# EDR_RFID_READER.net
KiCad netlist of a schematic drawn in Altium Designer
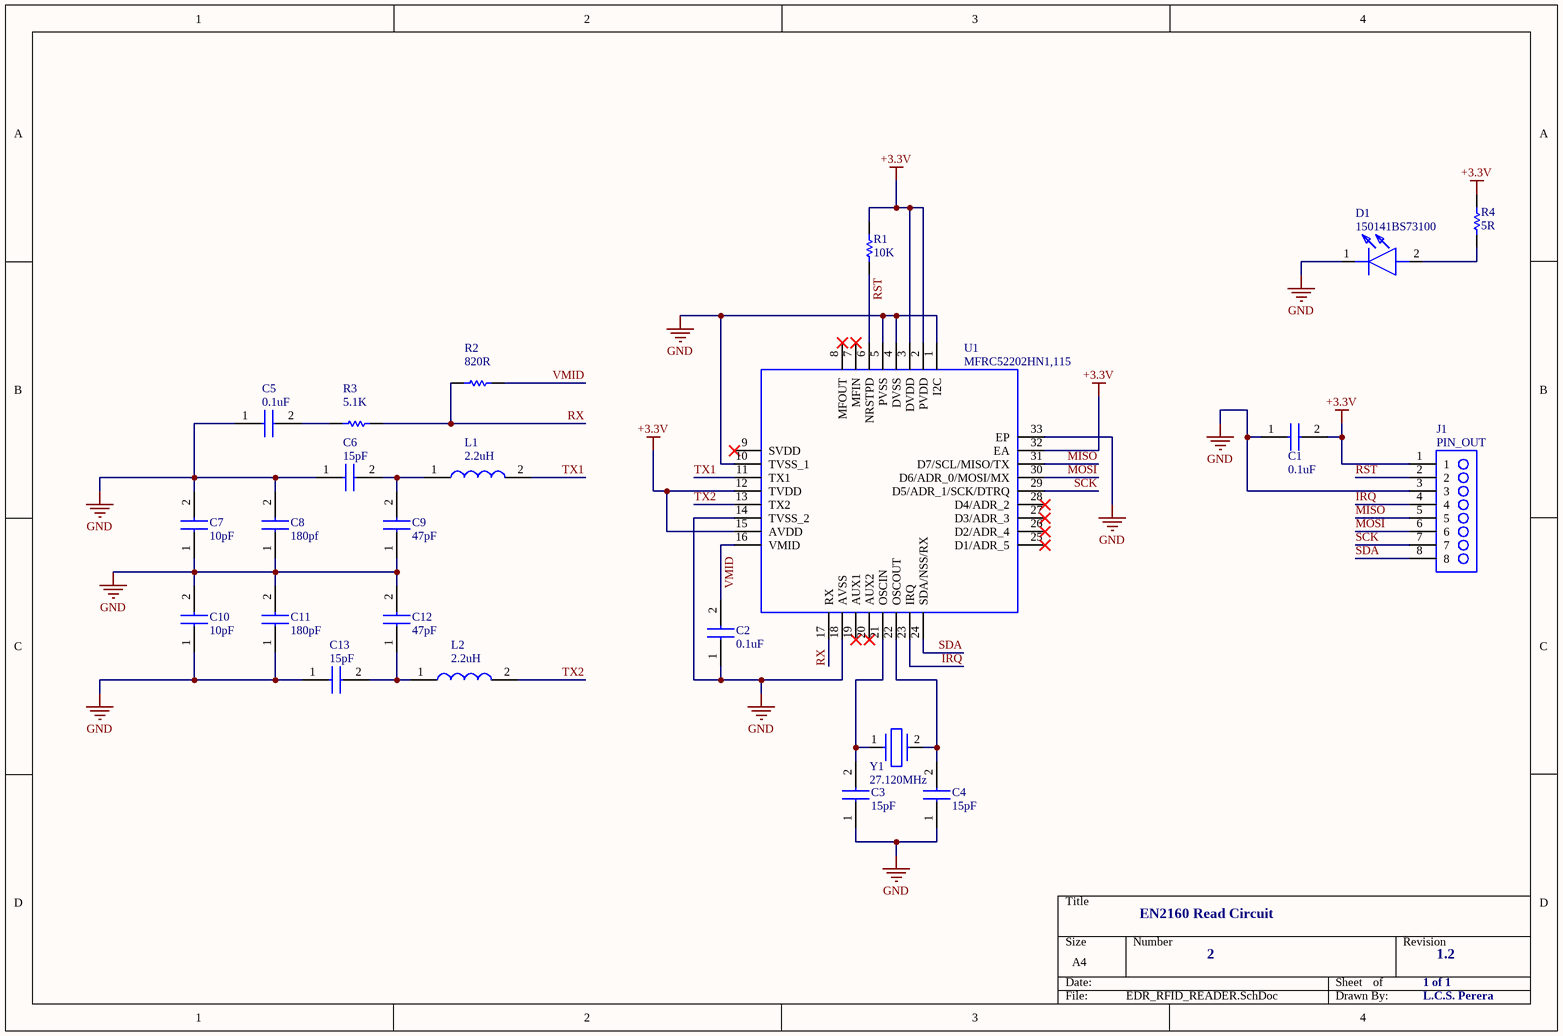
[diagram p0: EDR_RFID_READER.SchDoc]

(export (version "E")
  (design (tool "Eeschema 10.0.6"))
  (components
    (comp (ref "C1")
      (value "0.1uF")
      (footprint "0.1u")
      (description "Capacitor")
      (fields
        (field (name "MANUFACTURER_PART_NUMBER") "C0603C104K1RACTU")
        (field (name "MOUSER PART NUMBER") "80-C0603C104K1RACTU")
      )
      (libsource (lib "Schlib1") (part "0.1uF"))
    )
    (comp (ref "C2")
      (value "0.1uF")
      (footprint "0.1u")
      (description "Capacitor")
      (fields
        (field (name "MANUFACTURER_PART_NUMBER") "C0603C104K1RACTU")
        (field (name "MOUSER PART NUMBER") "80-C0603C104K1RACTU")
      )
      (libsource (lib "Schlib1") (part "0.1uF"))
    )
    (comp (ref "C3")
      (value "15pF")
      (footprint "15pf")
      (description "Capacitor")
      (fields
        (field (name "MANUFACTURER_PART_NUMBER") "C0805X150F4HACAUTO")
        (field (name "MOUSER PART NUMBER") "80-C0805X150F4HAUTO")
      )
      (libsource (lib "Schlib1") (part "C0805X150F4HACAUTO"))
    )
    (comp (ref "C4")
      (value "15pF")
      (footprint "15pf")
      (description "Capacitor")
      (fields
        (field (name "MANUFACTURER_PART_NUMBER") "C0805X150F4HACAUTO")
        (field (name "MOUSER PART NUMBER") "80-C0805X150F4HAUTO")
      )
      (libsource (lib "Schlib1") (part "C0805X150F4HACAUTO"))
    )
    (comp (ref "C5")
      (value "0.1uF")
      (footprint "0.1u")
      (description "Capacitor")
      (fields
        (field (name "MANUFACTURER_PART_NUMBER") "C0603C104K1RACTU")
        (field (name "MOUSER PART NUMBER") "80-C0603C104K1RACTU")
      )
      (libsource (lib "Schlib1") (part "0.1uF"))
    )
    (comp (ref "C6")
      (value "15pF")
      (footprint "15pf")
      (description "Capacitor")
      (fields
        (field (name "MANUFACTURER_PART_NUMBER") "C0805X150F4HACAUTO")
        (field (name "MOUSER PART NUMBER") "80-C0805X150F4HAUTO")
      )
      (libsource (lib "Schlib1") (part "C0805X150F4HACAUTO"))
    )
    (comp (ref "C7")
      (value "10pF")
      (footprint "10pf")
      (fields (field (name "MP") "C0805C100J5GACTU"))
      (libsource (lib "Schlib1") (part "C0805C100J5GACTU"))
    )
    (comp (ref "C8")
      (value "180pf")
      (footprint "15pf")
      (description "Capacitor")
      (fields (field (name "MANUFACTURER_PART_NUMBER") "C0805C181F1GACTU"))
      (libsource (lib "Schlib1") (part "C0805C181F1GACTU"))
    )
    (comp (ref "C9")
      (value "47pF")
      (footprint "47pf")
      (description "Capacitor")
      (fields
        (field (name "MANUFACTURER_PART_NUMBER") "C0805C470JDGACTU")
        (field (name "MOUSER PART NUMBER") "80-C0805C470JDG")
      )
      (libsource (lib "Schlib1") (part "C0805C470JDGACTU"))
    )
    (comp (ref "C10")
      (value "10pF")
      (footprint "10pf")
      (fields (field (name "MP") "C0805C100J5GACTU"))
      (libsource (lib "Schlib1") (part "C0805C100J5GACTU"))
    )
    (comp (ref "C11")
      (value "180pF")
      (footprint "15pf")
      (description "Capacitor")
      (fields (field (name "MANUFACTURER_PART_NUMBER") "C0805C181F1GACTU"))
      (libsource (lib "Schlib1") (part "C0805C181F1GACTU"))
    )
    (comp (ref "C12")
      (value "47pF")
      (footprint "47pf")
      (description "Capacitor")
      (fields
        (field (name "MANUFACTURER_PART_NUMBER") "C0805C470JDGACTU")
        (field (name "MOUSER PART NUMBER") "80-C0805C470JDG")
      )
      (libsource (lib "Schlib1") (part "C0805C470JDGACTU"))
    )
    (comp (ref "C13")
      (value "15pF")
      (footprint "15pf")
      (description "Capacitor")
      (fields
        (field (name "MANUFACTURER_PART_NUMBER") "C0805X150F4HACAUTO")
        (field (name "MOUSER PART NUMBER") "80-C0805X150F4HAUTO")
      )
      (libsource (lib "Schlib1") (part "C0805X150F4HACAUTO"))
    )
    (comp (ref "D1")
      (value "150141BS73100")
      (footprint "LEDM3528X210N")
      (description "LED")
      (fields (field (name "MOUSER PART NUMBER") "710-150141BS73100"))
      (libsource (lib "Schlib1") (part "150141BS73100"))
    )
    (comp (ref "J1")
      (value "PIN_OUT")
      (footprint "8X1")
      (description "Connector")
      (fields
        (field (name "MANUFACTURER_PART_NUMBER") "61300811121")
        (field (name "MOUSER PART NUMBER") "710-61300811121")
      )
      (libsource (lib "Schlib1") (part "61300811121_1"))
    )
    (comp (ref "L1")
      (value "2.2uH")
      (footprint "2.2U")
      (description "Inductor")
      (fields
        (field (name "MANUFACTURER_PART_NUMBER") "ASMPM-0806-2R2M-T")
        (field (name "MOUSER PART NUMBER") "815-ASMPM-0806-2.2MT")
      )
      (libsource (lib "Schlib1") (part "ASMPM-0806-2R2M-T"))
    )
    (comp (ref "L2")
      (value "2.2uH")
      (footprint "2.2U")
      (description "Inductor")
      (fields
        (field (name "MANUFACTURER_PART_NUMBER") "ASMPM-0806-2R2M-T")
        (field (name "MOUSER PART NUMBER") "815-ASMPM-0806-2.2MT")
      )
      (libsource (lib "Schlib1") (part "ASMPM-0806-2R2M-T"))
    )
    (comp (ref "R1")
      (value "10K")
      (footprint "10k")
      (description "Resistor")
      (fields
        (field (name "MANUFACTURER_PART_NUMBER") "CR0805-FX-1002ELF")
        (field (name "MOUSER PART NUMBER") "652-CR0805FX-1002ELF")
      )
      (libsource (lib "Schlib1") (part "CR0805-FX-1002ELF"))
    )
    (comp (ref "R2")
      (value "820R")
      (footprint "820")
      (description "Resistor")
      (fields (field (name "MANUFACTURER_PART_NUMBER") "0805W8F8200T5E"))
      (libsource (lib "Schlib1") (part "0805W8F8200T5E"))
    )
    (comp (ref "R3")
      (value "5.1K")
      (footprint "5.1k")
      (description "Resistor")
      (fields
        (field (name "MANUFACTURER_PART_NUMBER") "CR0805-FX-5101ELF")
        (field (name "MOUSER PART NUMBER") "652-CR0805FX-5101ELF")
      )
      (libsource (lib "Schlib1") (part "CR0805-FX-5101ELF"))
    )
    (comp (ref "R4")
      (value "5R")
      (footprint "1k")
      (description "Resistor")
      (fields
        (field (name "MANUFACTURER_PART_NUMBER") "CHP0805AFX-1002ELF")
        (field (name "MOUSER PART NUMBER") "652-CHP0805AFX1002EL")
      )
      (libsource (lib "Schlib1") (part "CHP0805AFX-1002ELF1k"))
    )
    (comp (ref "U1")
      (value "MFRC52202HN1,115")
      (footprint "MFRC522")
      (description "Integrated Circuit")
      (fields (field (name "MOUSER PART NUMBER") "771-MFRC52202HN1115"))
      (libsource (lib "Schlib1") (part "MFRC52202HN1,115"))
    )
    (comp (ref "Y1")
      (value "27.120MHz")
      (footprint "27.120")
      (description "Crystal or Oscillator")
      (fields
        (field (name "MANUFACTURER_PART_NUMBER") "ABLS-27.120MHZ-B4-F-T")
        (field (name "MOUSER PART NUMBER") "815-ABLS27120MHZB4FT")
      )
      (libsource (lib "Schlib1") (part "ABLS-27.120MHZ-B4-F-T"))
    )
  )
  (nets
    (net (code "1") (name "+3.3V") (class "Default")
      (node (ref "C1") (pin "2") (pinfunction "2_2") (pintype "passive"))
      (node (ref "J1") (pin "1") (pinfunction "1_1") (pintype "passive"))
      (node (ref "R1") (pin "2") (pinfunction "2_2") (pintype "passive"))
      (node (ref "R4") (pin "2") (pinfunction "2_2") (pintype "passive"))
      (node (ref "U1") (pin "12") (pinfunction "TVDD_12") (pintype "passive"))
      (node (ref "U1") (pin "15") (pinfunction "AVDD_15") (pintype "passive"))
      (node (ref "U1") (pin "2") (pinfunction "PVDD_2") (pintype "passive"))
      (node (ref "U1") (pin "3") (pinfunction "DVDD_3") (pintype "passive"))
      (node (ref "U1") (pin "32") (pinfunction "EA_32") (pintype "passive"))
    )
    (net (code "2") (name "/IRQ") (class "Default")
      (node (ref "J1") (pin "4") (pinfunction "4_4") (pintype "passive"))
      (node (ref "U1") (pin "23") (pinfunction "IRQ_23") (pintype "passive"))
    )
    (net (code "3") (name "/MISO") (class "Default")
      (node (ref "J1") (pin "5") (pinfunction "5_5") (pintype "passive"))
      (node (ref "U1") (pin "31") (pinfunction "D7/SCL/MISO/TX_31") (pintype "passive"))
    )
    (net (code "4") (name "/MOSI") (class "Default")
      (node (ref "J1") (pin "6") (pinfunction "6_6") (pintype "passive"))
      (node (ref "U1") (pin "30") (pinfunction "D6/ADR_0/MOSI/MX_30") (pintype "passive"))
    )
    (net (code "5") (name "/RST") (class "Default")
      (node (ref "J1") (pin "2") (pinfunction "2_2") (pintype "passive"))
      (node (ref "R1") (pin "1") (pinfunction "1_1") (pintype "passive"))
      (node (ref "U1") (pin "6") (pinfunction "NRSTPD_6") (pintype "passive"))
    )
    (net (code "6") (name "/RX") (class "Default")
      (node (ref "R2") (pin "1") (pinfunction "1_1") (pintype "passive"))
      (node (ref "R3") (pin "2") (pinfunction "2_2") (pintype "passive"))
      (node (ref "U1") (pin "17") (pinfunction "RX_17") (pintype "passive"))
    )
    (net (code "7") (name "/SCK") (class "Default")
      (node (ref "J1") (pin "7") (pinfunction "7_7") (pintype "passive"))
      (node (ref "U1") (pin "29") (pinfunction "D5/ADR_1/SCK/DTRQ_29") (pintype "passive"))
    )
    (net (code "8") (name "/SDA") (class "Default")
      (node (ref "J1") (pin "8") (pinfunction "8_8") (pintype "passive"))
      (node (ref "U1") (pin "24") (pinfunction "SDA/NSS/RX_24") (pintype "passive"))
    )
    (net (code "9") (name "/TX1") (class "Default")
      (node (ref "L1") (pin "2") (pinfunction "2_2") (pintype "passive"))
      (node (ref "U1") (pin "11") (pinfunction "TX1_11") (pintype "passive"))
    )
    (net (code "10") (name "/TX2") (class "Default")
      (node (ref "L2") (pin "2") (pinfunction "2_2") (pintype "passive"))
      (node (ref "U1") (pin "13") (pinfunction "TX2_13") (pintype "passive"))
    )
    (net (code "11") (name "/VMID") (class "Default")
      (node (ref "C2") (pin "2") (pinfunction "2_2") (pintype "passive"))
      (node (ref "R2") (pin "2") (pinfunction "2_2") (pintype "passive"))
      (node (ref "U1") (pin "16") (pinfunction "VMID_16") (pintype "passive"))
    )
    (net (code "12") (name "GND") (class "Default")
      (node (ref "C1") (pin "1") (pinfunction "1_1") (pintype "passive"))
      (node (ref "C10") (pin "1") (pinfunction "1_1") (pintype "passive"))
      (node (ref "C10") (pin "2") (pinfunction "2_2") (pintype "passive"))
      (node (ref "C11") (pin "1") (pinfunction "1_1") (pintype "passive"))
      (node (ref "C11") (pin "2") (pinfunction "2_2") (pintype "passive"))
      (node (ref "C12") (pin "2") (pinfunction "2_2") (pintype "passive"))
      (node (ref "C13") (pin "1") (pinfunction "1_1") (pintype "passive"))
      (node (ref "C2") (pin "1") (pinfunction "1_1") (pintype "passive"))
      (node (ref "C3") (pin "1") (pinfunction "1_1") (pintype "passive"))
      (node (ref "C4") (pin "1") (pinfunction "1_1") (pintype "passive"))
      (node (ref "C5") (pin "1") (pinfunction "1_1") (pintype "passive"))
      (node (ref "C6") (pin "1") (pinfunction "1_1") (pintype "passive"))
      (node (ref "C7") (pin "1") (pinfunction "1_1") (pintype "passive"))
      (node (ref "C7") (pin "2") (pinfunction "2_2") (pintype "passive"))
      (node (ref "C8") (pin "1") (pinfunction "1_1") (pintype "passive"))
      (node (ref "C8") (pin "2") (pinfunction "2_2") (pintype "passive"))
      (node (ref "C9") (pin "1") (pinfunction "1_1") (pintype "passive"))
      (node (ref "D1") (pin "1") (pinfunction "K_1") (pintype "passive"))
      (node (ref "J1") (pin "3") (pinfunction "3_3") (pintype "passive"))
      (node (ref "U1") (pin "1") (pinfunction "I2C_1") (pintype "passive"))
      (node (ref "U1") (pin "10") (pinfunction "TVSS_1_10") (pintype "passive"))
      (node (ref "U1") (pin "14") (pinfunction "TVSS_2_14") (pintype "passive"))
      (node (ref "U1") (pin "18") (pinfunction "AVSS_18") (pintype "passive"))
      (node (ref "U1") (pin "33") (pinfunction "EP_33") (pintype "passive"))
      (node (ref "U1") (pin "4") (pinfunction "DVSS_4") (pintype "passive"))
      (node (ref "U1") (pin "5") (pinfunction "PVSS_5") (pintype "passive"))
    )
    (net (code "13") (name "Net-(C5-Pad2)") (class "Default")
      (node (ref "C5") (pin "2") (pinfunction "2_2") (pintype "passive"))
      (node (ref "R3") (pin "1") (pinfunction "1_1") (pintype "passive"))
    )
    (net (code "14") (name "Net-(C6-Pad2)") (class "Default")
      (node (ref "C6") (pin "2") (pinfunction "2_2") (pintype "passive"))
      (node (ref "C9") (pin "2") (pinfunction "2_2") (pintype "passive"))
      (node (ref "L1") (pin "1") (pinfunction "1_1") (pintype "passive"))
    )
    (net (code "15") (name "Net-(C12-Pad1)") (class "Default")
      (node (ref "C12") (pin "1") (pinfunction "1_1") (pintype "passive"))
      (node (ref "C13") (pin "2") (pinfunction "2_2") (pintype "passive"))
      (node (ref "L2") (pin "1") (pinfunction "1_1") (pintype "passive"))
    )
    (net (code "16") (name "Net-(D1-A)") (class "Default")
      (node (ref "D1") (pin "2") (pinfunction "A_2") (pintype "passive"))
      (node (ref "R4") (pin "1") (pinfunction "1_1") (pintype "passive"))
    )
    (net (code "17") (name "Net-(U1-OSCIN)") (class "Default")
      (node (ref "C3") (pin "2") (pinfunction "2_2") (pintype "passive"))
      (node (ref "U1") (pin "21") (pinfunction "OSCIN_21") (pintype "passive"))
      (node (ref "Y1") (pin "1") (pinfunction "1_1") (pintype "passive"))
    )
    (net (code "18") (name "Net-(U1-OSCOUT)") (class "Default")
      (node (ref "C4") (pin "2") (pinfunction "2_2") (pintype "passive"))
      (node (ref "U1") (pin "22") (pinfunction "OSCOUT_22") (pintype "passive"))
      (node (ref "Y1") (pin "2") (pinfunction "2_2") (pintype "passive"))
    )
    (net (code "19") (name "unconnected-(U1-AUX1-Pad19)") (class "Default")
      (node (ref "U1") (pin "19") (pinfunction "AUX1_19") (pintype "passive+no_connect"))
    )
    (net (code "20") (name "unconnected-(U1-AUX2-Pad20)") (class "Default")
      (node (ref "U1") (pin "20") (pinfunction "AUX2_20") (pintype "passive+no_connect"))
    )
    (net (code "21") (name "unconnected-(U1-D1{slash}ADR_5-Pad25)") (class "Default")
      (node (ref "U1") (pin "25") (pinfunction "D1/ADR_5_25") (pintype "passive+no_connect"))
    )
    (net (code "22") (name "unconnected-(U1-D2{slash}ADR_4-Pad26)") (class "Default")
      (node (ref "U1") (pin "26") (pinfunction "D2/ADR_4_26") (pintype "passive+no_connect"))
    )
    (net (code "23") (name "unconnected-(U1-D3{slash}ADR_3-Pad27)") (class "Default")
      (node (ref "U1") (pin "27") (pinfunction "D3/ADR_3_27") (pintype "passive+no_connect"))
    )
    (net (code "24") (name "unconnected-(U1-D4{slash}ADR_2-Pad28)") (class "Default")
      (node (ref "U1") (pin "28") (pinfunction "D4/ADR_2_28") (pintype "passive+no_connect"))
    )
    (net (code "25") (name "unconnected-(U1-MFIN-Pad7)") (class "Default")
      (node (ref "U1") (pin "7") (pinfunction "MFIN_7") (pintype "passive+no_connect"))
    )
    (net (code "26") (name "unconnected-(U1-MFOUT-Pad8)") (class "Default")
      (node (ref "U1") (pin "8") (pinfunction "MFOUT_8") (pintype "passive+no_connect"))
    )
    (net (code "27") (name "unconnected-(U1-SVDD-Pad9)") (class "Default")
      (node (ref "U1") (pin "9") (pinfunction "SVDD_9") (pintype "passive+no_connect"))
    )
  )
)
